# edition4-mainpart.net
KiCad netlist of a schematic drawn in EAGLE
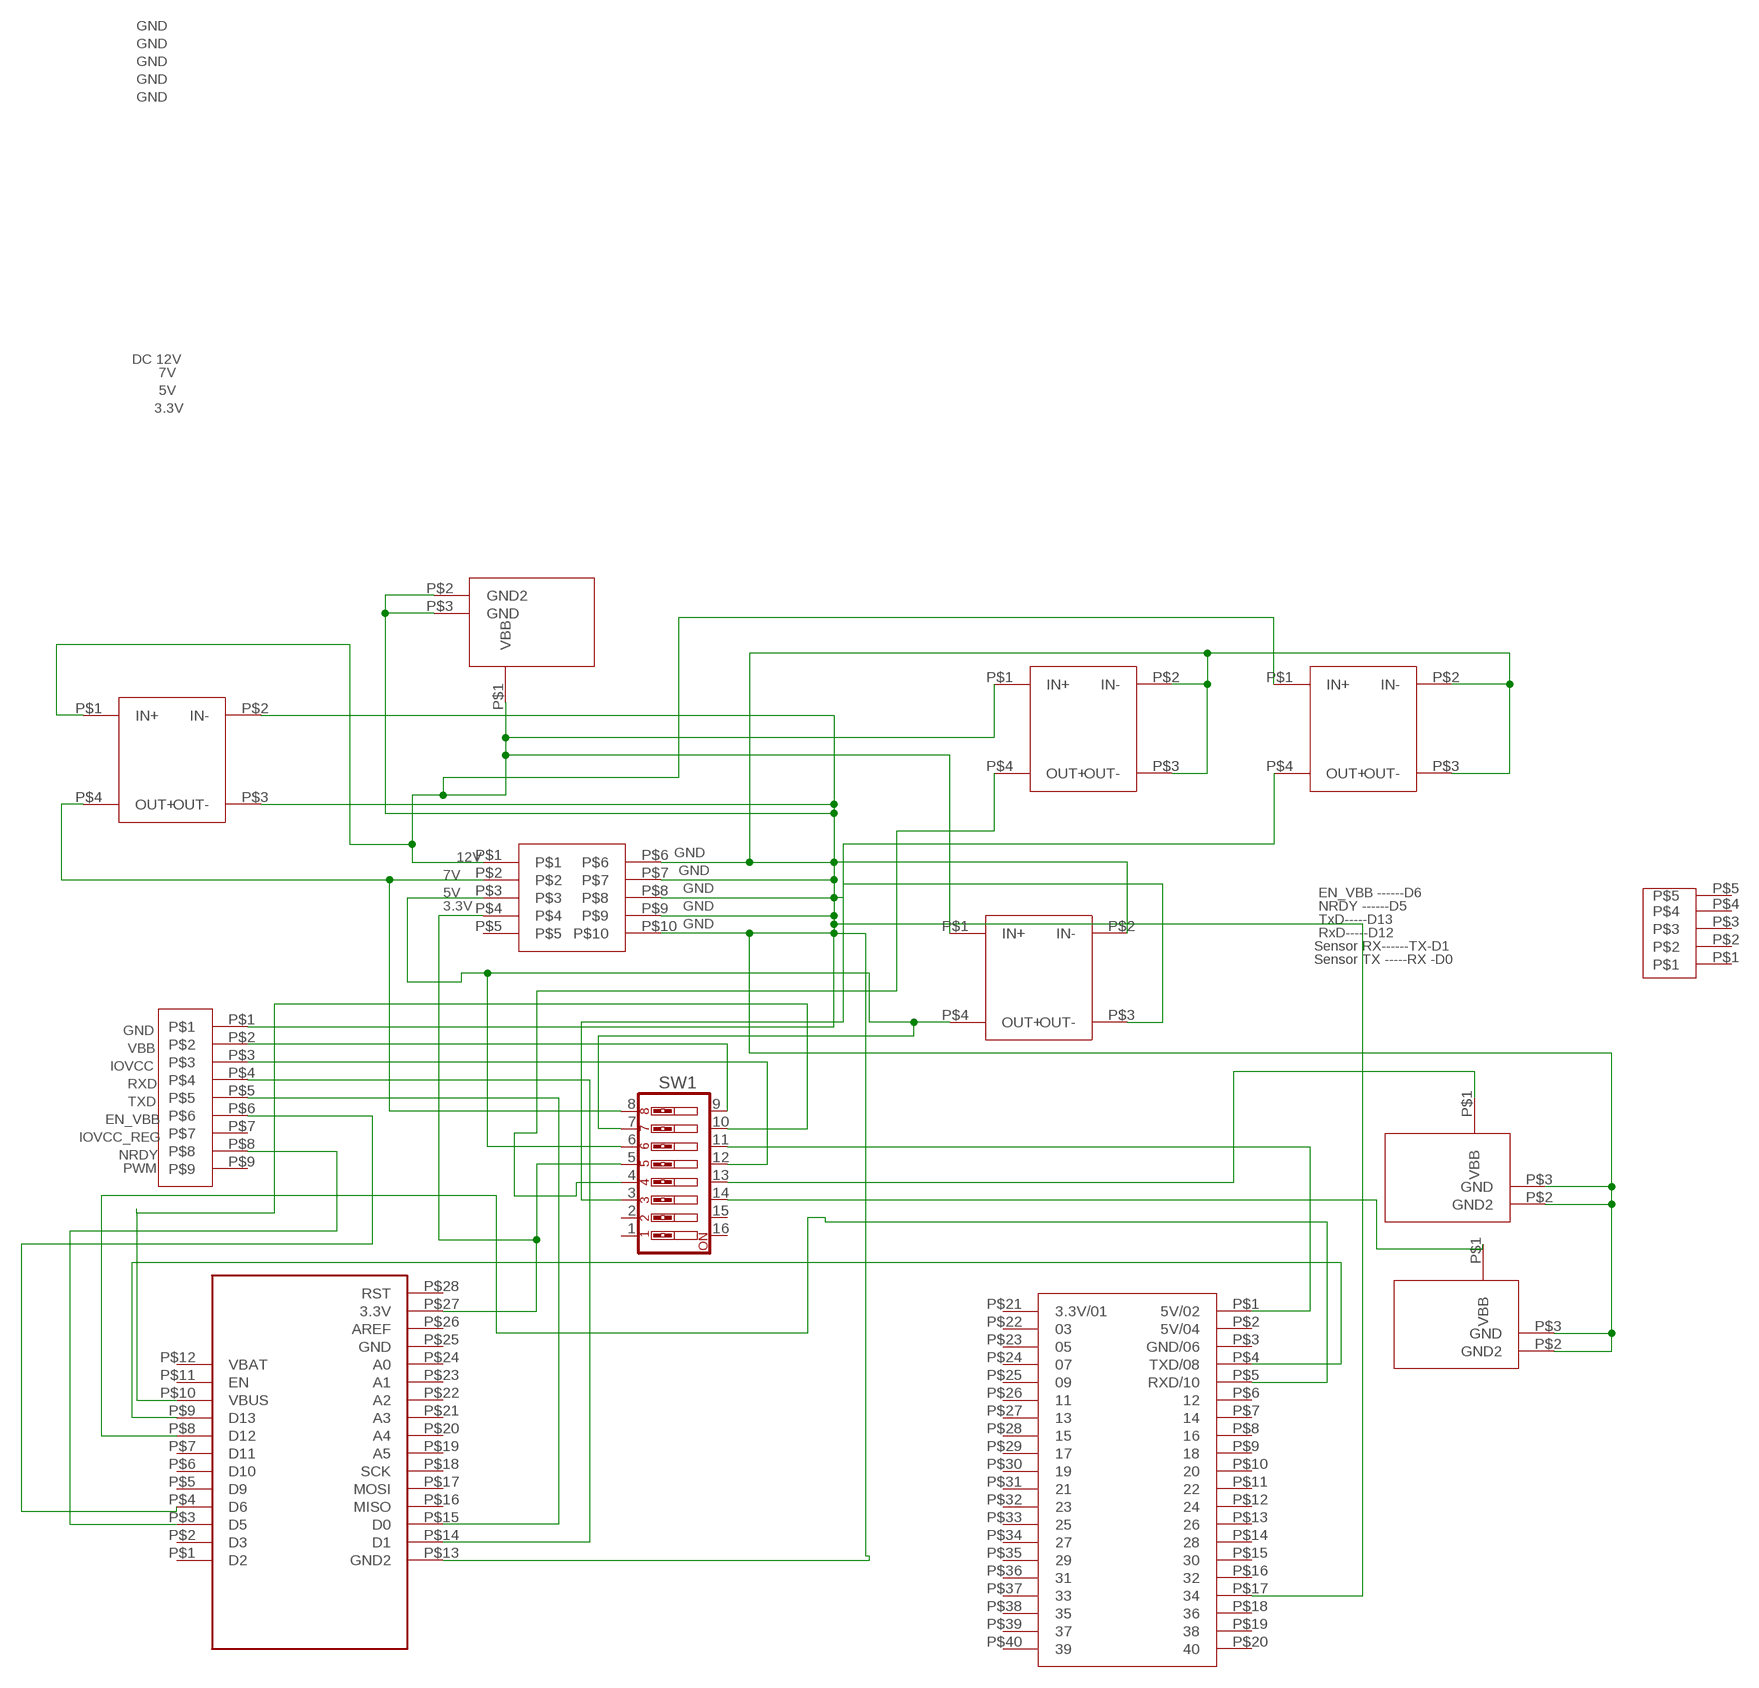
[diagram p0: schematic, sheet 1]

(export (version "E")
  (design (tool "Eeschema 10.0.6"))
  (components
    (comp (ref "SW1")
      (value "SW_DIP-8")
      (footprint "eagle-import:EDG-08")
      (libsource (lib "eagle-import") (part "SW_DIP-8"))
    )
    (comp (ref "U$1")
      (value "MH-MINI-360")
      (footprint "eagle-import:MH-MINI-360")
      (libsource (lib "eagle-import") (part "MH-MINI-360"))
    )
    (comp (ref "U$2")
      (value "MH-MINI-360")
      (footprint "eagle-import:MH-MINI-360")
      (libsource (lib "eagle-import") (part "MH-MINI-360"))
    )
    (comp (ref "U$3")
      (value "POWER")
      (footprint "eagle-import:POWERIN")
      (libsource (lib "eagle-import") (part "POWER"))
    )
    (comp (ref "U$4")
      (value "POWER")
      (footprint "eagle-import:POWERIN")
      (libsource (lib "eagle-import") (part "POWER"))
    )
    (comp (ref "U$5")
      (value "POWER")
      (footprint "eagle-import:POWERIN")
      (libsource (lib "eagle-import") (part "POWER"))
    )
    (comp (ref "U$6")
      (value "MH-MINI-360")
      (footprint "eagle-import:MH-MINI-360")
      (libsource (lib "eagle-import") (part "MH-MINI-360"))
    )
    (comp (ref "U$7")
      (value "MH-MINI-360")
      (footprint "eagle-import:MH-MINI-360")
      (libsource (lib "eagle-import") (part "MH-MINI-360"))
    )
    (comp (ref "U$8")
      (value "PIN")
      (footprint "eagle-import:PIN")
      (libsource (lib "eagle-import") (part "PIN"))
    )
    (comp (ref "U$10")
      (value "FEATHER")
      (footprint "eagle-import:FEATHER")
      (libsource (lib "eagle-import") (part "FEATHER"))
    )
    (comp (ref "U$11")
      (value "RASPBERRYPI")
      (footprint "eagle-import:RASPBERRYPI")
      (libsource (lib "eagle-import") (part "RASPBERRYPI"))
    )
    (comp (ref "U$14")
      (value "2X5FEET")
      (footprint "eagle-import:2X5FEET")
      (libsource (lib "eagle-import") (part "2X5FEET"))
    )
    (comp (ref "U$15")
      (value "9FEETPIN")
      (footprint "eagle-import:9FEETPIN")
      (libsource (lib "eagle-import") (part "9FEETPIN"))
    )
  )
  (nets
    (net (code "1") (name "Net-(SW1-Pad9)") (class "Default")
      (node (ref "SW1") (pin "9") (pinfunction "9_9") (pintype "passive"))
      (node (ref "U$15") (pin "P$2") (pinfunction "P$2_P$2") (pintype "bidirectional"))
    )
    (net (code "2") (name "Net-(SW1-Pad12)") (class "Default")
      (node (ref "SW1") (pin "12") (pinfunction "12_12") (pintype "passive"))
      (node (ref "U$15") (pin "P$3") (pinfunction "P$3_P$3") (pintype "bidirectional"))
    )
    (net (code "3") (name "Net-(U$1-IN+)") (class "Default")
      (node (ref "U$1") (pin "P$1") (pinfunction "IN+_P$1") (pintype "bidirectional"))
      (node (ref "U$14") (pin "P$1") (pinfunction "P$1_P$1") (pintype "bidirectional"))
      (node (ref "U$2") (pin "P$1") (pinfunction "IN+_P$1") (pintype "bidirectional"))
      (node (ref "U$3") (pin "P$1") (pinfunction "VBB_P$1") (pintype "bidirectional"))
      (node (ref "U$6") (pin "P$1") (pinfunction "IN+_P$1") (pintype "bidirectional"))
      (node (ref "U$7") (pin "P$1") (pinfunction "IN+_P$1") (pintype "bidirectional"))
    )
    (net (code "4") (name "Net-(U$1-IN-)") (class "Default")
      (node (ref "U$1") (pin "P$2") (pinfunction "IN-_P$2") (pintype "bidirectional"))
      (node (ref "U$1") (pin "P$3") (pinfunction "OUT-_P$3") (pintype "bidirectional"))
      (node (ref "U$10") (pin "P$13") (pinfunction "GND2_P$13") (pintype "bidirectional"))
      (node (ref "U$11") (pin "P$17") (pinfunction "34_P$17") (pintype "bidirectional"))
      (node (ref "U$14") (pin "P$10") (pinfunction "P$10_P$10") (pintype "bidirectional"))
      (node (ref "U$14") (pin "P$6") (pinfunction "P$6_P$6") (pintype "bidirectional"))
      (node (ref "U$14") (pin "P$7") (pinfunction "P$7_P$7") (pintype "bidirectional"))
      (node (ref "U$14") (pin "P$8") (pinfunction "P$8_P$8") (pintype "bidirectional"))
      (node (ref "U$14") (pin "P$9") (pinfunction "P$9_P$9") (pintype "bidirectional"))
      (node (ref "U$15") (pin "P$1") (pinfunction "P$1_P$1") (pintype "bidirectional"))
      (node (ref "U$2") (pin "P$2") (pinfunction "IN-_P$2") (pintype "bidirectional"))
      (node (ref "U$2") (pin "P$3") (pinfunction "OUT-_P$3") (pintype "bidirectional"))
      (node (ref "U$3") (pin "P$2") (pinfunction "GND2_P$2") (pintype "bidirectional"))
      (node (ref "U$3") (pin "P$3") (pinfunction "GND_P$3") (pintype "bidirectional"))
      (node (ref "U$4") (pin "P$2") (pinfunction "GND2_P$2") (pintype "bidirectional"))
      (node (ref "U$4") (pin "P$3") (pinfunction "GND_P$3") (pintype "bidirectional"))
      (node (ref "U$5") (pin "P$2") (pinfunction "GND2_P$2") (pintype "bidirectional"))
      (node (ref "U$5") (pin "P$3") (pinfunction "GND_P$3") (pintype "bidirectional"))
      (node (ref "U$6") (pin "P$2") (pinfunction "IN-_P$2") (pintype "bidirectional"))
      (node (ref "U$6") (pin "P$3") (pinfunction "OUT-_P$3") (pintype "bidirectional"))
      (node (ref "U$7") (pin "P$2") (pinfunction "IN-_P$2") (pintype "bidirectional"))
      (node (ref "U$7") (pin "P$3") (pinfunction "OUT-_P$3") (pintype "bidirectional"))
    )
    (net (code "5") (name "Net-(U$1-OUT+)") (class "Default")
      (node (ref "SW1") (pin "4") (pinfunction "4_4") (pintype "passive"))
      (node (ref "U$1") (pin "P$4") (pinfunction "OUT+_P$4") (pintype "bidirectional"))
    )
    (net (code "6") (name "Net-(U$2-OUT+)") (class "Default")
      (node (ref "SW1") (pin "6") (pinfunction "6_6") (pintype "passive"))
      (node (ref "SW1") (pin "7") (pinfunction "7_7") (pintype "passive"))
      (node (ref "U$14") (pin "P$3") (pinfunction "P$3_P$3") (pintype "bidirectional"))
      (node (ref "U$2") (pin "P$4") (pinfunction "OUT+_P$4") (pintype "bidirectional"))
    )
    (net (code "7") (name "Net-(U$4-VBB)") (class "Default")
      (node (ref "SW1") (pin "14") (pinfunction "14_14") (pintype "passive"))
      (node (ref "U$4") (pin "P$1") (pinfunction "VBB_P$1") (pintype "bidirectional"))
    )
    (net (code "8") (name "Net-(U$5-VBB)") (class "Default")
      (node (ref "SW1") (pin "13") (pinfunction "13_13") (pintype "passive"))
      (node (ref "U$5") (pin "P$1") (pinfunction "VBB_P$1") (pintype "bidirectional"))
    )
    (net (code "9") (name "Net-(U$6-OUT+)") (class "Default")
      (node (ref "SW1") (pin "8") (pinfunction "8_8") (pintype "passive"))
      (node (ref "U$14") (pin "P$2") (pinfunction "P$2_P$2") (pintype "bidirectional"))
      (node (ref "U$6") (pin "P$4") (pinfunction "OUT+_P$4") (pintype "bidirectional"))
    )
    (net (code "10") (name "Net-(U$7-OUT+)") (class "Default")
      (node (ref "SW1") (pin "3") (pinfunction "3_3") (pintype "passive"))
      (node (ref "U$7") (pin "P$4") (pinfunction "OUT+_P$4") (pintype "bidirectional"))
    )
    (net (code "11") (name "Net-(U$10-3.3V)") (class "Default")
      (node (ref "SW1") (pin "5") (pinfunction "5_5") (pintype "passive"))
      (node (ref "U$10") (pin "P$27") (pinfunction "3.3V_P$27") (pintype "bidirectional"))
      (node (ref "U$14") (pin "P$4") (pinfunction "P$4_P$4") (pintype "bidirectional"))
    )
    (net (code "12") (name "Net-(U$10-D0)") (class "Default")
      (node (ref "U$10") (pin "P$15") (pinfunction "D0_P$15") (pintype "bidirectional"))
      (node (ref "U$15") (pin "P$5") (pinfunction "P$5_P$5") (pintype "bidirectional"))
    )
    (net (code "13") (name "Net-(U$10-D1)") (class "Default")
      (node (ref "U$10") (pin "P$14") (pinfunction "D1_P$14") (pintype "bidirectional"))
      (node (ref "U$15") (pin "P$4") (pinfunction "P$4_P$4") (pintype "bidirectional"))
    )
    (net (code "14") (name "Net-(U$10-D5)") (class "Default")
      (node (ref "U$10") (pin "P$3") (pinfunction "D5_P$3") (pintype "bidirectional"))
      (node (ref "U$15") (pin "P$8") (pinfunction "P$8_P$8") (pintype "bidirectional"))
    )
    (net (code "15") (name "Net-(U$10-D6)") (class "Default")
      (node (ref "U$10") (pin "P$4") (pinfunction "D6_P$4") (pintype "bidirectional"))
      (node (ref "U$15") (pin "P$6") (pinfunction "P$6_P$6") (pintype "bidirectional"))
    )
    (net (code "16") (name "Net-(U$10-D12)") (class "Default")
      (node (ref "U$10") (pin "P$8") (pinfunction "D12_P$8") (pintype "bidirectional"))
      (node (ref "U$11") (pin "P$5") (pinfunction "RXD/10_P$5") (pintype "bidirectional"))
    )
    (net (code "17") (name "Net-(U$10-D13)") (class "Default")
      (node (ref "U$10") (pin "P$9") (pinfunction "D13_P$9") (pintype "bidirectional"))
      (node (ref "U$11") (pin "P$4") (pinfunction "TXD/08_P$4") (pintype "bidirectional"))
    )
    (net (code "18") (name "Net-(U$10-VBUS)") (class "Default")
      (node (ref "SW1") (pin "10") (pinfunction "10_10") (pintype "passive"))
      (node (ref "U$10") (pin "P$10") (pinfunction "VBUS_P$10") (pintype "bidirectional"))
    )
    (net (code "19") (name "Net-(U$11-5V{slash}02)") (class "Default")
      (node (ref "SW1") (pin "11") (pinfunction "11_11") (pintype "passive"))
      (node (ref "U$11") (pin "P$1") (pinfunction "5V/02_P$1") (pintype "bidirectional"))
    )
    (net (code "20") (name "unconnected-(SW1-Pad1)") (class "Default")
      (node (ref "SW1") (pin "1") (pinfunction "1_1") (pintype "passive"))
    )
    (net (code "21") (name "unconnected-(SW1-Pad2)") (class "Default")
      (node (ref "SW1") (pin "2") (pinfunction "2_2") (pintype "passive"))
    )
    (net (code "22") (name "unconnected-(SW1-Pad15)") (class "Default")
      (node (ref "SW1") (pin "15") (pinfunction "15_15") (pintype "passive"))
    )
    (net (code "23") (name "unconnected-(SW1-Pad16)") (class "Default")
      (node (ref "SW1") (pin "16") (pinfunction "16_16") (pintype "passive"))
    )
    (net (code "24") (name "unconnected-(U$8-PadP$1)") (class "Default")
      (node (ref "U$8") (pin "P$1") (pinfunction "P$1_P$1") (pintype "bidirectional"))
    )
    (net (code "25") (name "unconnected-(U$8-PadP$2)") (class "Default")
      (node (ref "U$8") (pin "P$2") (pinfunction "P$2_P$2") (pintype "bidirectional"))
    )
    (net (code "26") (name "unconnected-(U$8-PadP$3)") (class "Default")
      (node (ref "U$8") (pin "P$3") (pinfunction "P$3_P$3") (pintype "bidirectional"))
    )
    (net (code "27") (name "unconnected-(U$8-PadP$4)") (class "Default")
      (node (ref "U$8") (pin "P$4") (pinfunction "P$4_P$4") (pintype "bidirectional"))
    )
    (net (code "28") (name "unconnected-(U$8-PadP$5)") (class "Default")
      (node (ref "U$8") (pin "P$5") (pinfunction "P$5_P$5") (pintype "bidirectional"))
    )
    (net (code "29") (name "unconnected-(U$10-A0-PadP$24)") (class "Default")
      (node (ref "U$10") (pin "P$24") (pinfunction "A0_P$24") (pintype "bidirectional"))
    )
    (net (code "30") (name "unconnected-(U$10-A1-PadP$23)") (class "Default")
      (node (ref "U$10") (pin "P$23") (pinfunction "A1_P$23") (pintype "bidirectional"))
    )
    (net (code "31") (name "unconnected-(U$10-A2-PadP$22)") (class "Default")
      (node (ref "U$10") (pin "P$22") (pinfunction "A2_P$22") (pintype "bidirectional"))
    )
    (net (code "32") (name "unconnected-(U$10-A3-PadP$21)") (class "Default")
      (node (ref "U$10") (pin "P$21") (pinfunction "A3_P$21") (pintype "bidirectional"))
    )
    (net (code "33") (name "unconnected-(U$10-A4-PadP$20)") (class "Default")
      (node (ref "U$10") (pin "P$20") (pinfunction "A4_P$20") (pintype "bidirectional"))
    )
    (net (code "34") (name "unconnected-(U$10-A5-PadP$19)") (class "Default")
      (node (ref "U$10") (pin "P$19") (pinfunction "A5_P$19") (pintype "bidirectional"))
    )
    (net (code "35") (name "unconnected-(U$10-AREF-PadP$26)") (class "Default")
      (node (ref "U$10") (pin "P$26") (pinfunction "AREF_P$26") (pintype "bidirectional"))
    )
    (net (code "36") (name "unconnected-(U$10-D2-PadP$1)") (class "Default")
      (node (ref "U$10") (pin "P$1") (pinfunction "D2_P$1") (pintype "bidirectional"))
    )
    (net (code "37") (name "unconnected-(U$10-D3-PadP$2)") (class "Default")
      (node (ref "U$10") (pin "P$2") (pinfunction "D3_P$2") (pintype "bidirectional"))
    )
    (net (code "38") (name "unconnected-(U$10-D9-PadP$5)") (class "Default")
      (node (ref "U$10") (pin "P$5") (pinfunction "D9_P$5") (pintype "bidirectional"))
    )
    (net (code "39") (name "unconnected-(U$10-D10-PadP$6)") (class "Default")
      (node (ref "U$10") (pin "P$6") (pinfunction "D10_P$6") (pintype "bidirectional"))
    )
    (net (code "40") (name "unconnected-(U$10-D11-PadP$7)") (class "Default")
      (node (ref "U$10") (pin "P$7") (pinfunction "D11_P$7") (pintype "bidirectional"))
    )
    (net (code "41") (name "unconnected-(U$10-EN-PadP$11)") (class "Default")
      (node (ref "U$10") (pin "P$11") (pinfunction "EN_P$11") (pintype "bidirectional"))
    )
    (net (code "42") (name "unconnected-(U$10-GND-PadP$25)") (class "Default")
      (node (ref "U$10") (pin "P$25") (pinfunction "GND_P$25") (pintype "bidirectional"))
    )
    (net (code "43") (name "unconnected-(U$10-MISO-PadP$16)") (class "Default")
      (node (ref "U$10") (pin "P$16") (pinfunction "MISO_P$16") (pintype "bidirectional"))
    )
    (net (code "44") (name "unconnected-(U$10-MOSI-PadP$17)") (class "Default")
      (node (ref "U$10") (pin "P$17") (pinfunction "MOSI_P$17") (pintype "bidirectional"))
    )
    (net (code "45") (name "unconnected-(U$10-RST-PadP$28)") (class "Default")
      (node (ref "U$10") (pin "P$28") (pinfunction "RST_P$28") (pintype "bidirectional"))
    )
    (net (code "46") (name "unconnected-(U$10-SCK-PadP$18)") (class "Default")
      (node (ref "U$10") (pin "P$18") (pinfunction "SCK_P$18") (pintype "bidirectional"))
    )
    (net (code "47") (name "unconnected-(U$10-VBAT-PadP$12)") (class "Default")
      (node (ref "U$10") (pin "P$12") (pinfunction "VBAT_P$12") (pintype "bidirectional"))
    )
    (net (code "48") (name "unconnected-(U$11-03-PadP$22)") (class "Default")
      (node (ref "U$11") (pin "P$22") (pinfunction "03_P$22") (pintype "bidirectional"))
    )
    (net (code "49") (name "unconnected-(U$11-3.3V{slash}01-PadP$21)") (class "Default")
      (node (ref "U$11") (pin "P$21") (pinfunction "3.3V/01_P$21") (pintype "bidirectional"))
    )
    (net (code "50") (name "unconnected-(U$11-05-PadP$23)") (class "Default")
      (node (ref "U$11") (pin "P$23") (pinfunction "05_P$23") (pintype "bidirectional"))
    )
    (net (code "51") (name "unconnected-(U$11-5V{slash}04-PadP$2)") (class "Default")
      (node (ref "U$11") (pin "P$2") (pinfunction "5V/04_P$2") (pintype "bidirectional"))
    )
    (net (code "52") (name "unconnected-(U$11-07-PadP$24)") (class "Default")
      (node (ref "U$11") (pin "P$24") (pinfunction "07_P$24") (pintype "bidirectional"))
    )
    (net (code "53") (name "unconnected-(U$11-09-PadP$25)") (class "Default")
      (node (ref "U$11") (pin "P$25") (pinfunction "09_P$25") (pintype "bidirectional"))
    )
    (net (code "54") (name "unconnected-(U$11-11-PadP$26)") (class "Default")
      (node (ref "U$11") (pin "P$26") (pinfunction "11_P$26") (pintype "bidirectional"))
    )
    (net (code "55") (name "unconnected-(U$11-12-PadP$6)") (class "Default")
      (node (ref "U$11") (pin "P$6") (pinfunction "12_P$6") (pintype "bidirectional"))
    )
    (net (code "56") (name "unconnected-(U$11-13-PadP$27)") (class "Default")
      (node (ref "U$11") (pin "P$27") (pinfunction "13_P$27") (pintype "bidirectional"))
    )
    (net (code "57") (name "unconnected-(U$11-14-PadP$7)") (class "Default")
      (node (ref "U$11") (pin "P$7") (pinfunction "14_P$7") (pintype "bidirectional"))
    )
    (net (code "58") (name "unconnected-(U$11-15-PadP$28)") (class "Default")
      (node (ref "U$11") (pin "P$28") (pinfunction "15_P$28") (pintype "bidirectional"))
    )
    (net (code "59") (name "unconnected-(U$11-16-PadP$8)") (class "Default")
      (node (ref "U$11") (pin "P$8") (pinfunction "16_P$8") (pintype "bidirectional"))
    )
    (net (code "60") (name "unconnected-(U$11-17-PadP$29)") (class "Default")
      (node (ref "U$11") (pin "P$29") (pinfunction "17_P$29") (pintype "bidirectional"))
    )
    (net (code "61") (name "unconnected-(U$11-18-PadP$9)") (class "Default")
      (node (ref "U$11") (pin "P$9") (pinfunction "18_P$9") (pintype "bidirectional"))
    )
    (net (code "62") (name "unconnected-(U$11-19-PadP$30)") (class "Default")
      (node (ref "U$11") (pin "P$30") (pinfunction "19_P$30") (pintype "bidirectional"))
    )
    (net (code "63") (name "unconnected-(U$11-20-PadP$10)") (class "Default")
      (node (ref "U$11") (pin "P$10") (pinfunction "20_P$10") (pintype "bidirectional"))
    )
    (net (code "64") (name "unconnected-(U$11-21-PadP$31)") (class "Default")
      (node (ref "U$11") (pin "P$31") (pinfunction "21_P$31") (pintype "bidirectional"))
    )
    (net (code "65") (name "unconnected-(U$11-22-PadP$11)") (class "Default")
      (node (ref "U$11") (pin "P$11") (pinfunction "22_P$11") (pintype "bidirectional"))
    )
    (net (code "66") (name "unconnected-(U$11-23-PadP$32)") (class "Default")
      (node (ref "U$11") (pin "P$32") (pinfunction "23_P$32") (pintype "bidirectional"))
    )
    (net (code "67") (name "unconnected-(U$11-24-PadP$12)") (class "Default")
      (node (ref "U$11") (pin "P$12") (pinfunction "24_P$12") (pintype "bidirectional"))
    )
    (net (code "68") (name "unconnected-(U$11-25-PadP$33)") (class "Default")
      (node (ref "U$11") (pin "P$33") (pinfunction "25_P$33") (pintype "bidirectional"))
    )
    (net (code "69") (name "unconnected-(U$11-26-PadP$13)") (class "Default")
      (node (ref "U$11") (pin "P$13") (pinfunction "26_P$13") (pintype "bidirectional"))
    )
    (net (code "70") (name "unconnected-(U$11-27-PadP$34)") (class "Default")
      (node (ref "U$11") (pin "P$34") (pinfunction "27_P$34") (pintype "bidirectional"))
    )
    (net (code "71") (name "unconnected-(U$11-28-PadP$14)") (class "Default")
      (node (ref "U$11") (pin "P$14") (pinfunction "28_P$14") (pintype "bidirectional"))
    )
    (net (code "72") (name "unconnected-(U$11-29-PadP$35)") (class "Default")
      (node (ref "U$11") (pin "P$35") (pinfunction "29_P$35") (pintype "bidirectional"))
    )
    (net (code "73") (name "unconnected-(U$11-30-PadP$15)") (class "Default")
      (node (ref "U$11") (pin "P$15") (pinfunction "30_P$15") (pintype "bidirectional"))
    )
    (net (code "74") (name "unconnected-(U$11-31-PadP$36)") (class "Default")
      (node (ref "U$11") (pin "P$36") (pinfunction "31_P$36") (pintype "bidirectional"))
    )
    (net (code "75") (name "unconnected-(U$11-32-PadP$16)") (class "Default")
      (node (ref "U$11") (pin "P$16") (pinfunction "32_P$16") (pintype "bidirectional"))
    )
    (net (code "76") (name "unconnected-(U$11-33-PadP$37)") (class "Default")
      (node (ref "U$11") (pin "P$37") (pinfunction "33_P$37") (pintype "bidirectional"))
    )
    (net (code "77") (name "unconnected-(U$11-35-PadP$38)") (class "Default")
      (node (ref "U$11") (pin "P$38") (pinfunction "35_P$38") (pintype "bidirectional"))
    )
    (net (code "78") (name "unconnected-(U$11-36-PadP$18)") (class "Default")
      (node (ref "U$11") (pin "P$18") (pinfunction "36_P$18") (pintype "bidirectional"))
    )
    (net (code "79") (name "unconnected-(U$11-37-PadP$39)") (class "Default")
      (node (ref "U$11") (pin "P$39") (pinfunction "37_P$39") (pintype "bidirectional"))
    )
    (net (code "80") (name "unconnected-(U$11-38-PadP$19)") (class "Default")
      (node (ref "U$11") (pin "P$19") (pinfunction "38_P$19") (pintype "bidirectional"))
    )
    (net (code "81") (name "unconnected-(U$11-39-PadP$40)") (class "Default")
      (node (ref "U$11") (pin "P$40") (pinfunction "39_P$40") (pintype "bidirectional"))
    )
    (net (code "82") (name "unconnected-(U$11-40-PadP$20)") (class "Default")
      (node (ref "U$11") (pin "P$20") (pinfunction "40_P$20") (pintype "bidirectional"))
    )
    (net (code "83") (name "unconnected-(U$11-GND{slash}06-PadP$3)") (class "Default")
      (node (ref "U$11") (pin "P$3") (pinfunction "GND/06_P$3") (pintype "bidirectional"))
    )
    (net (code "84") (name "unconnected-(U$14-PadP$5)") (class "Default")
      (node (ref "U$14") (pin "P$5") (pinfunction "P$5_P$5") (pintype "bidirectional"))
    )
    (net (code "85") (name "unconnected-(U$15-PadP$7)") (class "Default")
      (node (ref "U$15") (pin "P$7") (pinfunction "P$7_P$7") (pintype "bidirectional"))
    )
    (net (code "86") (name "unconnected-(U$15-PadP$9)") (class "Default")
      (node (ref "U$15") (pin "P$9") (pinfunction "P$9_P$9") (pintype "bidirectional"))
    )
  )
)
